# BG1094_Connector.net
KiCad netlist of a schematic drawn in Altium Designer
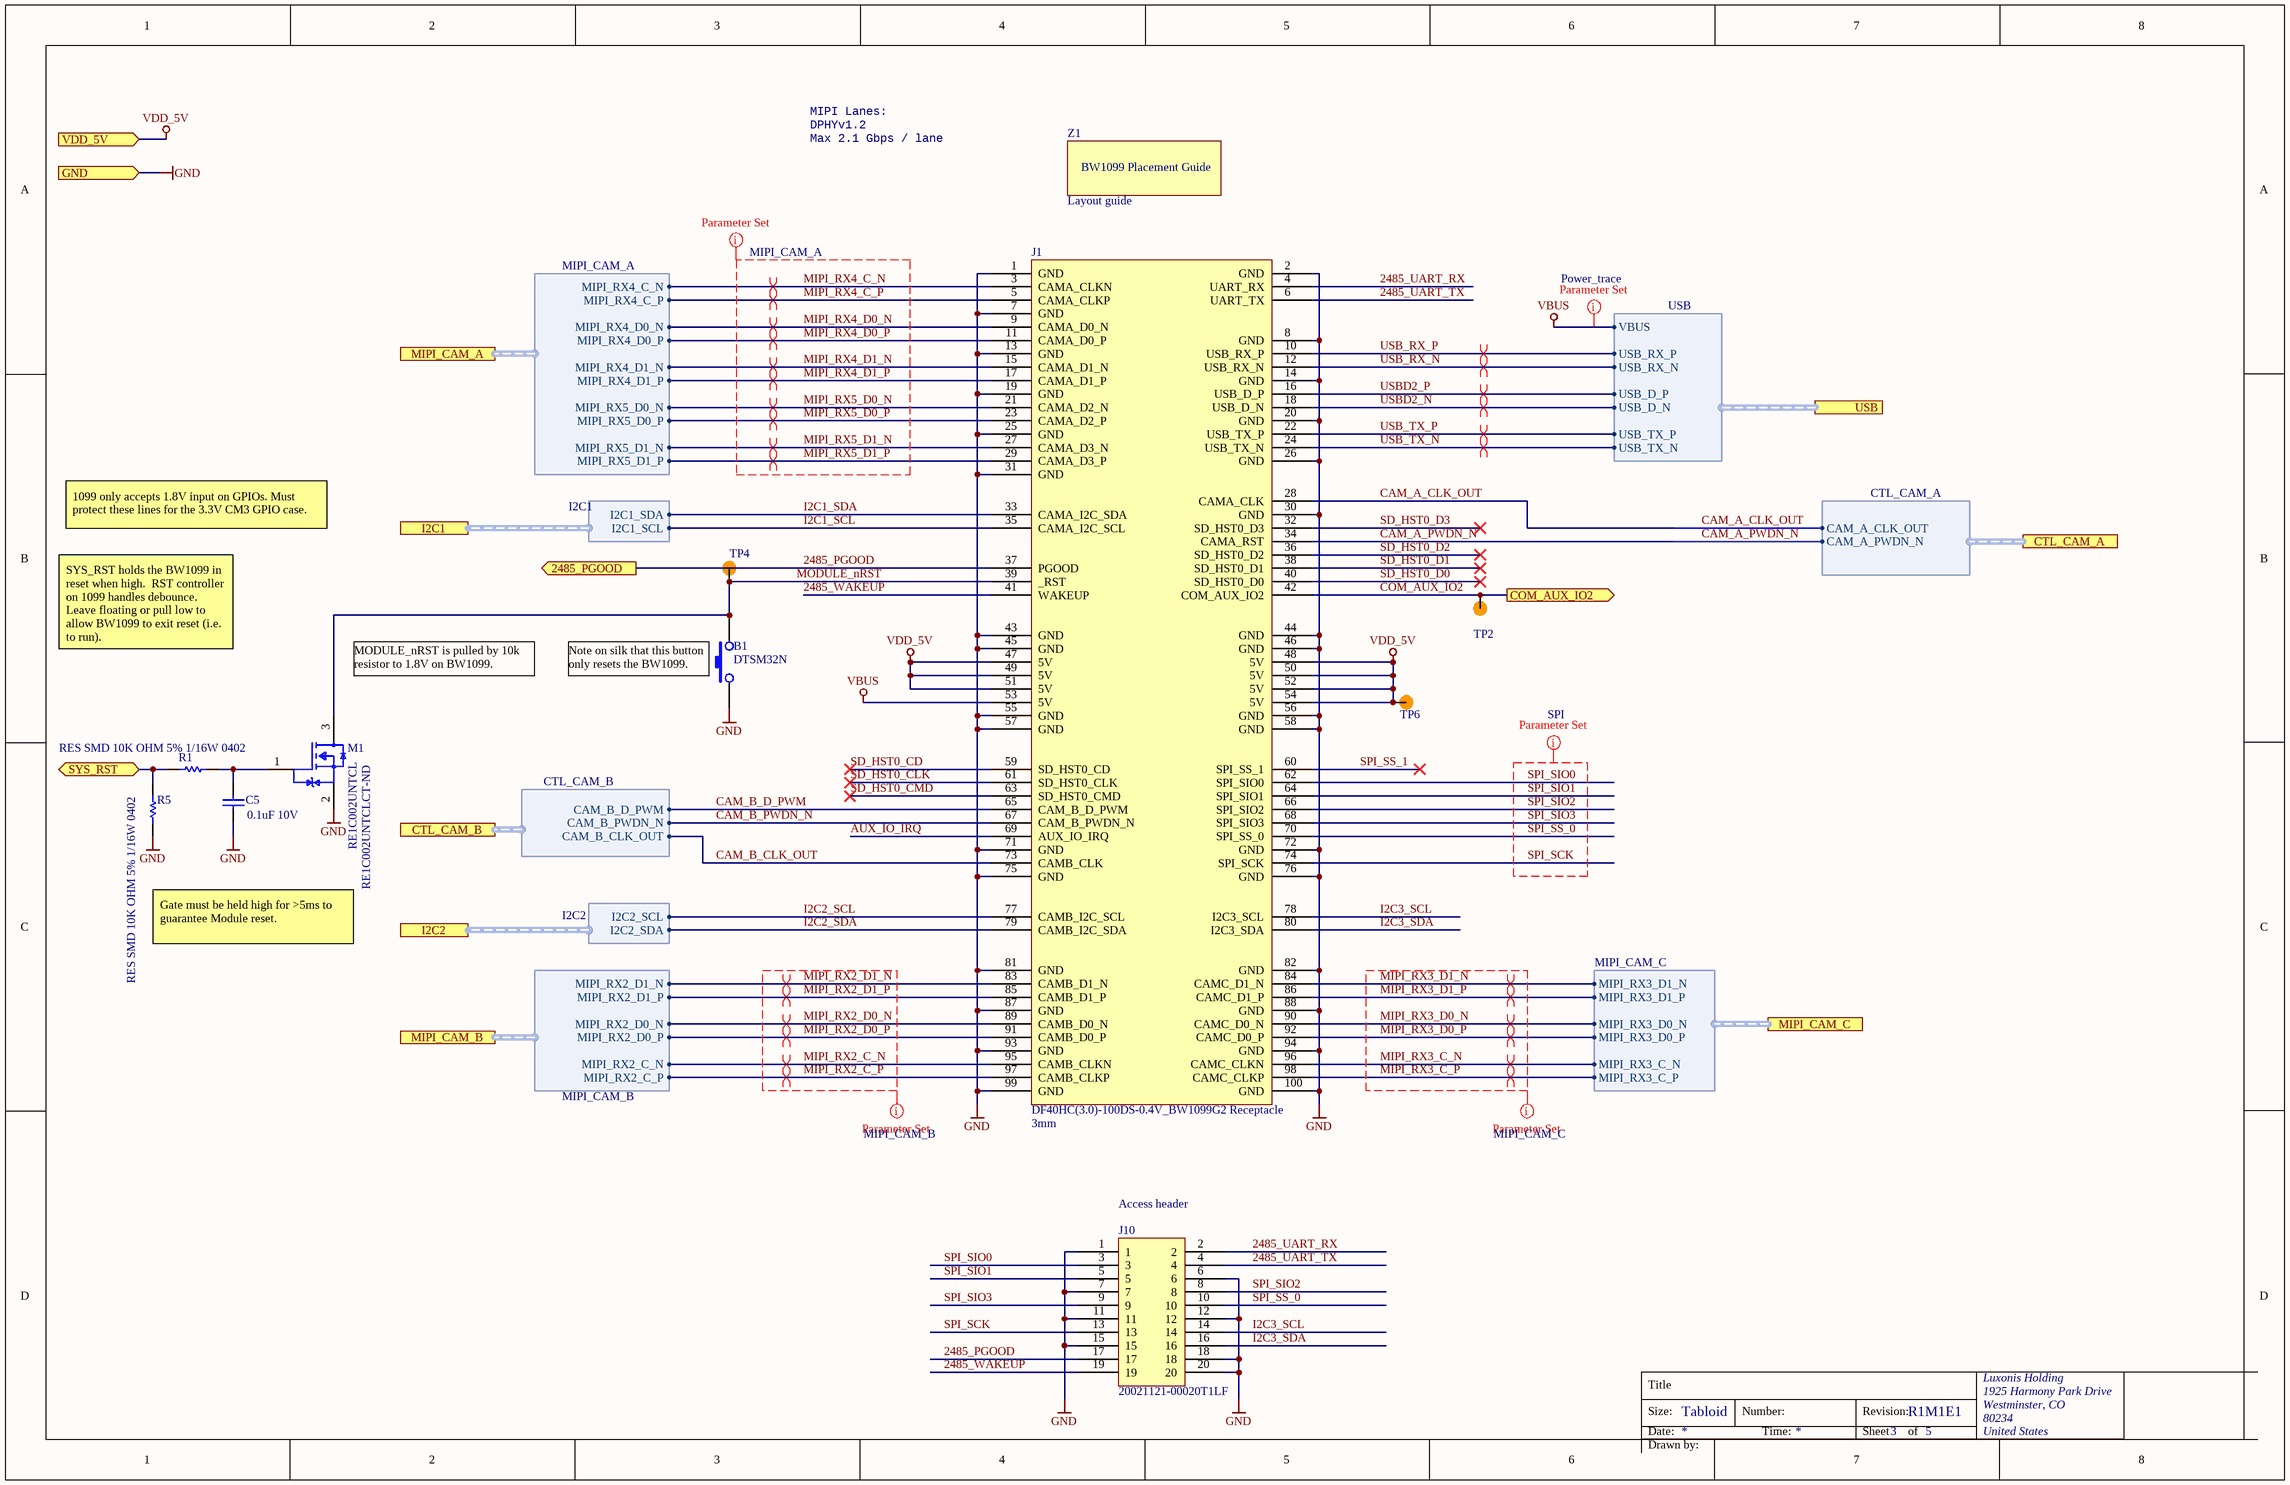
[diagram p0: BG1094_Connector.SchDoc]

(export (version "E")
  (design (tool "Eeschema 10.0.6"))
  (components
    (comp (ref "B1")
      (value "DTSM32N")
      (footprint "DTSM32N")
      (description "Tact Switch")
      (libsource (lib "MV0235_R4M0E0") (part "SW-PB"))
    )
    (comp (ref "C5")
      (value "0.1uF 10V")
      (footprint "IPC_RES_CAP:CAPC0402(1005)70_N")
      (description "0.1uF 10V X7R 10% Pad SMD 0402 125C T/R")
      (fields (field (name "TOLERANCE") "10%") (field (name "VOLTAGE") "10V"))
      (libsource (lib "Luxonis") (part "!CAP"))
    )
    (comp (ref "J1")
      (value "DF40HC(3.0)-100DS-0.4V_BW1099G2 Receptacle")
      (footprint "LuxonisMaster:DF40HC-3.0-100DS-0.4V_minpad")
      (description "CONN RCPT 100POS 0.4MM SMD GOLD")
      (fields (field (name "MATED STACKING HEIGHT") "3mm"))
      (libsource (lib "LuxonisMaster") (part "DF40HC(3.0)-100DS-0.4V_BW1099_G2"))
    )
    (comp (ref "J10")
      (value "20021121-00020T1LF")
      (footprint "BG1094:20021121-00020T1LF")
      (description "Conn Unshrouded Header HDR 20 POS 1.27mm Solder ST SMD Tube")
      (libsource (lib "BG1094") (part "20021121-00020T1LF"))
    )
    (comp (ref "M1")
      (value "RE1C002UNTCL")
      (footprint "Luxonis:SOT-416FL")
      (description "MOSFET N-CH 20V 0.2A EMT3")
      (fields (field (name "SUPPLIER PART NUMBER 1") "RE1C002UNTCLCT-ND"))
      (libsource (lib "Luxonis") (part "RE1C002UNTCL"))
    )
    (comp (ref "R1")
      (value "RES SMD 10K OHM 5% 1/16W 0402")
      (footprint "RESC0402(1005)_N")
      (libsource (lib "Luxonis") (part "!RES"))
    )
    (comp (ref "R5")
      (value "RES SMD 10K OHM 5% 1/16W 0402")
      (footprint "RESC0402(1005)_N")
      (libsource (lib "Luxonis") (part "!RES"))
    )
    (comp (ref "TP2")
      (value "TP100_200_NS")
      (footprint "LuxonisMaster:TP100_200_NS")
      (libsource (lib "LuxonisMaster") (part "TEST_POINT"))
    )
    (comp (ref "TP4")
      (value "TP_SMD")
      (footprint "TP_0.75MM_SMD_NO-SILK")
      (description "circular pad test point, SMD")
      (libsource (lib "Luxonis") (part "TP_SMD"))
    )
    (comp (ref "TP6")
      (value "TP_SMD")
      (footprint "TP_0.75MM_SMD_NO-SILK")
      (description "circular pad test point, SMD")
      (libsource (lib "Luxonis") (part "TP_SMD"))
    )
    (comp (ref "Z1")
      (value "Layout guide")
      (footprint "Luxonis:BW1099_Footprint")
      (description "Use for aligning BW1099 mount")
      (libsource (lib "Luxonis") (part "BW1099_Footprint"))
    )
  )
  (nets
    (net (code "9") (name "/2485_PGOOD") (class "Default")
      (node (ref "J1") (pin "37") (pinfunction "PGOOD_37") (pintype "passive"))
      (node (ref "J10") (pin "17") (pinfunction "17_17") (pintype "passive"))
    )
    (net (code "10") (name "/2485_UART_RX") (class "Default")
      (node (ref "J1") (pin "4") (pinfunction "UART_RX_4") (pintype "passive"))
      (node (ref "J10") (pin "2") (pinfunction "2_2") (pintype "passive"))
    )
    (net (code "11") (name "/2485_UART_TX") (class "Default")
      (node (ref "J1") (pin "6") (pinfunction "UART_TX_6") (pintype "passive"))
      (node (ref "J10") (pin "4") (pinfunction "4_4") (pintype "passive"))
    )
    (net (code "12") (name "/2485_WAKEUP") (class "Default")
      (node (ref "J1") (pin "41") (pinfunction "WAKEUP_41") (pintype "passive"))
      (node (ref "J10") (pin "19") (pinfunction "19_19") (pintype "passive"))
    )
    (net (code "13") (name "/AUX_IO_IRQ") (class "Default")
      (node (ref "J1") (pin "69") (pinfunction "AUX_IO_IRQ_69") (pintype "passive"))
    )
    (net (code "14") (name "/CAM_A_CLK_OUT") (class "Default")
      (node (ref "J1") (pin "28") (pinfunction "CAMA_CLK_28") (pintype "passive"))
    )
    (net (code "15") (name "/CAM_A_PWDN_N") (class "Default")
      (node (ref "J1") (pin "34") (pinfunction "CAMA_RST_34") (pintype "passive"))
    )
    (net (code "16") (name "/CAM_B_CLK_OUT") (class "Default")
      (node (ref "J1") (pin "73") (pinfunction "CAMB_CLK_73") (pintype "passive"))
    )
    (net (code "17") (name "/CAM_B_D_PWM") (class "Default")
      (node (ref "J1") (pin "65") (pinfunction "CAM_B_D_PWM_65") (pintype "passive"))
    )
    (net (code "18") (name "/CAM_B_PWDN_N") (class "Default")
      (node (ref "J1") (pin "67") (pinfunction "CAM_B_PWDN_N_67") (pintype "passive"))
    )
    (net (code "19") (name "/COM_AUX_IO2") (class "Default")
      (node (ref "J1") (pin "42") (pinfunction "COM_AUX_IO2_42") (pintype "passive"))
      (node (ref "TP2") (pin "1") (pintype "passive"))
    )
    (net (code "20") (name "/I2C1_SCL") (class "Default")
      (node (ref "J1") (pin "35") (pinfunction "CAMA_I2C_SCL_35") (pintype "passive"))
    )
    (net (code "21") (name "/I2C1_SDA") (class "Default")
      (node (ref "J1") (pin "33") (pinfunction "CAMA_I2C_SDA_33") (pintype "passive"))
    )
    (net (code "22") (name "/I2C2_SCL") (class "Default")
      (node (ref "J1") (pin "77") (pinfunction "CAMB_I2C_SCL_77") (pintype "passive"))
    )
    (net (code "23") (name "/I2C2_SDA") (class "Default")
      (node (ref "J1") (pin "79") (pinfunction "CAMB_I2C_SDA_79") (pintype "passive"))
    )
    (net (code "24") (name "/I2C3_SCL") (class "Default")
      (node (ref "J1") (pin "78") (pinfunction "I2C3_SCL_78") (pintype "passive"))
      (node (ref "J10") (pin "14") (pinfunction "14_14") (pintype "passive"))
    )
    (net (code "25") (name "/I2C3_SDA") (class "Default")
      (node (ref "J1") (pin "80") (pinfunction "I2C3_SDA_80") (pintype "passive"))
      (node (ref "J10") (pin "16") (pinfunction "16_16") (pintype "passive"))
    )
    (net (code "26") (name "/MIPI_RX2_C_N") (class "Default")
      (node (ref "J1") (pin "95") (pinfunction "CAMB_CLKN_95") (pintype "passive"))
    )
    (net (code "27") (name "/MIPI_RX2_C_P") (class "Default")
      (node (ref "J1") (pin "97") (pinfunction "CAMB_CLKP_97") (pintype "passive"))
    )
    (net (code "28") (name "/MIPI_RX2_D0_N") (class "Default")
      (node (ref "J1") (pin "89") (pinfunction "CAMB_D0_N_89") (pintype "passive"))
    )
    (net (code "29") (name "/MIPI_RX2_D0_P") (class "Default")
      (node (ref "J1") (pin "91") (pinfunction "CAMB_D0_P_91") (pintype "passive"))
    )
    (net (code "30") (name "/MIPI_RX2_D1_N") (class "Default")
      (node (ref "J1") (pin "83") (pinfunction "CAMB_D1_N_83") (pintype "passive"))
    )
    (net (code "31") (name "/MIPI_RX2_D1_P") (class "Default")
      (node (ref "J1") (pin "85") (pinfunction "CAMB_D1_P_85") (pintype "passive"))
    )
    (net (code "32") (name "/MIPI_RX3_C_N") (class "Default")
      (node (ref "J1") (pin "96") (pinfunction "CAMC_CLKN_96") (pintype "passive"))
    )
    (net (code "33") (name "/MIPI_RX3_C_P") (class "Default")
      (node (ref "J1") (pin "98") (pinfunction "CAMC_CLKP_98") (pintype "passive"))
    )
    (net (code "34") (name "/MIPI_RX3_D0_N") (class "Default")
      (node (ref "J1") (pin "90") (pinfunction "CAMC_D0_N_90") (pintype "passive"))
    )
    (net (code "35") (name "/MIPI_RX3_D0_P") (class "Default")
      (node (ref "J1") (pin "92") (pinfunction "CAMC_D0_P_92") (pintype "passive"))
    )
    (net (code "36") (name "/MIPI_RX3_D1_N") (class "Default")
      (node (ref "J1") (pin "84") (pinfunction "CAMC_D1_N_84") (pintype "passive"))
    )
    (net (code "37") (name "/MIPI_RX3_D1_P") (class "Default")
      (node (ref "J1") (pin "86") (pinfunction "CAMC_D1_P_86") (pintype "passive"))
    )
    (net (code "38") (name "/MIPI_RX4_C_N") (class "Default")
      (node (ref "J1") (pin "3") (pinfunction "CAMA_CLKN_3") (pintype "passive"))
    )
    (net (code "39") (name "/MIPI_RX4_C_P") (class "Default")
      (node (ref "J1") (pin "5") (pinfunction "CAMA_CLKP_5") (pintype "passive"))
    )
    (net (code "40") (name "/MIPI_RX4_D0_N") (class "Default")
      (node (ref "J1") (pin "9") (pinfunction "CAMA_D0_N_9") (pintype "passive"))
    )
    (net (code "41") (name "/MIPI_RX4_D0_P") (class "Default")
      (node (ref "J1") (pin "11") (pinfunction "CAMA_D0_P_11") (pintype "passive"))
    )
    (net (code "42") (name "/MIPI_RX4_D1_N") (class "Default")
      (node (ref "J1") (pin "15") (pinfunction "CAMA_D1_N_15") (pintype "passive"))
    )
    (net (code "43") (name "/MIPI_RX4_D1_P") (class "Default")
      (node (ref "J1") (pin "17") (pinfunction "CAMA_D1_P_17") (pintype "passive"))
    )
    (net (code "44") (name "/MIPI_RX5_D0_N") (class "Default")
      (node (ref "J1") (pin "21") (pinfunction "CAMA_D2_N_21") (pintype "passive"))
    )
    (net (code "45") (name "/MIPI_RX5_D0_P") (class "Default")
      (node (ref "J1") (pin "23") (pinfunction "CAMA_D2_P_23") (pintype "passive"))
    )
    (net (code "46") (name "/MIPI_RX5_D1_N") (class "Default")
      (node (ref "J1") (pin "27") (pinfunction "CAMA_D3_N_27") (pintype "passive"))
    )
    (net (code "47") (name "/MIPI_RX5_D1_P") (class "Default")
      (node (ref "J1") (pin "29") (pinfunction "CAMA_D3_P_29") (pintype "passive"))
    )
    (net (code "48") (name "/MODULE_nRST") (class "Default")
      (node (ref "B1") (pin "2") (pinfunction "2_2") (pintype "passive"))
      (node (ref "J1") (pin "39") (pinfunction "_RST_39") (pintype "passive"))
      (node (ref "M1") (pin "3") (pinfunction "Drain_3") (pintype "passive"))
      (node (ref "TP4") (pin "1") (pintype "passive"))
    )
    (net (code "49") (name "/SD_HST0_CD") (class "Default")
      (node (ref "J1") (pin "59") (pinfunction "SD_HST0_CD_59") (pintype "passive+no_connect"))
    )
    (net (code "50") (name "/SD_HST0_CLK") (class "Default")
      (node (ref "J1") (pin "61") (pinfunction "SD_HST0_CLK_61") (pintype "passive+no_connect"))
    )
    (net (code "51") (name "/SD_HST0_CMD") (class "Default")
      (node (ref "J1") (pin "63") (pinfunction "SD_HST0_CMD_63") (pintype "passive+no_connect"))
    )
    (net (code "52") (name "/SD_HST0_D0") (class "Default")
      (node (ref "J1") (pin "40") (pinfunction "SD_HST0_D0_40") (pintype "passive+no_connect"))
    )
    (net (code "53") (name "/SD_HST0_D1") (class "Default")
      (node (ref "J1") (pin "38") (pinfunction "SD_HST0_D1_38") (pintype "passive+no_connect"))
    )
    (net (code "54") (name "/SD_HST0_D2") (class "Default")
      (node (ref "J1") (pin "36") (pinfunction "SD_HST0_D2_36") (pintype "passive+no_connect"))
    )
    (net (code "55") (name "/SD_HST0_D3") (class "Default")
      (node (ref "J1") (pin "32") (pinfunction "SD_HST0_D3_32") (pintype "passive+no_connect"))
    )
    (net (code "56") (name "/SPI_SCK") (class "Default")
      (node (ref "J1") (pin "74") (pinfunction "SPI_SCK_74") (pintype "passive"))
      (node (ref "J10") (pin "13") (pinfunction "13_13") (pintype "passive"))
    )
    (net (code "57") (name "/SPI_SIO0") (class "Default")
      (node (ref "J1") (pin "62") (pinfunction "SPI_SIO0_62") (pintype "passive"))
      (node (ref "J10") (pin "3") (pinfunction "3_3") (pintype "passive"))
    )
    (net (code "58") (name "/SPI_SIO1") (class "Default")
      (node (ref "J1") (pin "64") (pinfunction "SPI_SIO1_64") (pintype "passive"))
      (node (ref "J10") (pin "5") (pinfunction "5_5") (pintype "passive"))
    )
    (net (code "59") (name "/SPI_SIO2") (class "Default")
      (node (ref "J1") (pin "66") (pinfunction "SPI_SIO2_66") (pintype "passive"))
      (node (ref "J10") (pin "8") (pinfunction "8_8") (pintype "passive"))
    )
    (net (code "60") (name "/SPI_SIO3") (class "Default")
      (node (ref "J1") (pin "68") (pinfunction "SPI_SIO3_68") (pintype "passive"))
      (node (ref "J10") (pin "9") (pinfunction "9_9") (pintype "passive"))
    )
    (net (code "61") (name "/SPI_SS_0") (class "Default")
      (node (ref "J1") (pin "70") (pinfunction "SPI_SS_0_70") (pintype "passive"))
      (node (ref "J10") (pin "10") (pinfunction "10_10") (pintype "passive"))
    )
    (net (code "62") (name "/SPI_SS_1") (class "Default")
      (node (ref "J1") (pin "60") (pinfunction "SPI_SS_1_60") (pintype "passive+no_connect"))
    )
    (net (code "63") (name "/SYS_RST") (class "Default")
      (node (ref "R1") (pin "2") (pinfunction "2_2") (pintype "passive"))
      (node (ref "R5") (pin "2") (pinfunction "2_2") (pintype "passive"))
    )
    (net (code "64") (name "/USBD2_N") (class "Default")
      (node (ref "J1") (pin "18") (pinfunction "USB_D_N_18") (pintype "passive"))
    )
    (net (code "65") (name "/USBD2_P") (class "Default")
      (node (ref "J1") (pin "16") (pinfunction "USB_D_P_16") (pintype "passive"))
    )
    (net (code "66") (name "/USB_RX_N") (class "Default")
      (node (ref "J1") (pin "12") (pinfunction "USB_RX_N_12") (pintype "passive"))
    )
    (net (code "67") (name "/USB_RX_P") (class "Default")
      (node (ref "J1") (pin "10") (pinfunction "USB_RX_P_10") (pintype "passive"))
    )
    (net (code "68") (name "/USB_TX_N") (class "Default")
      (node (ref "J1") (pin "24") (pinfunction "USB_TX_N_24") (pintype "passive"))
    )
    (net (code "69") (name "/USB_TX_P") (class "Default")
      (node (ref "J1") (pin "22") (pinfunction "USB_TX_P_22") (pintype "passive"))
    )
    (net (code "78") (name "GND") (class "Default")
      (node (ref "B1") (pin "1") (pinfunction "1_1") (pintype "passive"))
      (node (ref "C5") (pin "1") (pinfunction "1_1") (pintype "passive"))
      (node (ref "J1") (pin "1") (pinfunction "GND_1") (pintype "passive"))
      (node (ref "J1") (pin "100") (pinfunction "GND_100") (pintype "passive"))
      (node (ref "J1") (pin "13") (pinfunction "GND_13") (pintype "passive"))
      (node (ref "J1") (pin "14") (pinfunction "GND_14") (pintype "passive"))
      (node (ref "J1") (pin "19") (pinfunction "GND_19") (pintype "passive"))
      (node (ref "J1") (pin "2") (pinfunction "GND_2") (pintype "passive"))
      (node (ref "J1") (pin "20") (pinfunction "GND_20") (pintype "passive"))
      (node (ref "J1") (pin "25") (pinfunction "GND_25") (pintype "passive"))
      (node (ref "J1") (pin "26") (pinfunction "GND_26") (pintype "passive"))
      (node (ref "J1") (pin "30") (pinfunction "GND_30") (pintype "passive"))
      (node (ref "J1") (pin "31") (pinfunction "GND_31") (pintype "passive"))
      (node (ref "J1") (pin "43") (pinfunction "GND_43") (pintype "passive"))
      (node (ref "J1") (pin "44") (pinfunction "GND_44") (pintype "passive"))
      (node (ref "J1") (pin "45") (pinfunction "GND_45") (pintype "passive"))
      (node (ref "J1") (pin "46") (pinfunction "GND_46") (pintype "passive"))
      (node (ref "J1") (pin "55") (pinfunction "GND_55") (pintype "passive"))
      (node (ref "J1") (pin "56") (pinfunction "GND_56") (pintype "passive"))
      (node (ref "J1") (pin "57") (pinfunction "GND_57") (pintype "passive"))
      (node (ref "J1") (pin "58") (pinfunction "GND_58") (pintype "passive"))
      (node (ref "J1") (pin "7") (pinfunction "GND_7") (pintype "passive"))
      (node (ref "J1") (pin "71") (pinfunction "GND_71") (pintype "passive"))
      (node (ref "J1") (pin "72") (pinfunction "GND_72") (pintype "passive"))
      (node (ref "J1") (pin "75") (pinfunction "GND_75") (pintype "passive"))
      (node (ref "J1") (pin "76") (pinfunction "GND_76") (pintype "passive"))
      (node (ref "J1") (pin "8") (pinfunction "GND_8") (pintype "passive"))
      (node (ref "J1") (pin "81") (pinfunction "GND_81") (pintype "passive"))
      (node (ref "J1") (pin "82") (pinfunction "GND_82") (pintype "passive"))
      (node (ref "J1") (pin "87") (pinfunction "GND_87") (pintype "passive"))
      (node (ref "J1") (pin "88") (pinfunction "GND_88") (pintype "passive"))
      (node (ref "J1") (pin "93") (pinfunction "GND_93") (pintype "passive"))
      (node (ref "J1") (pin "94") (pinfunction "GND_94") (pintype "passive"))
      (node (ref "J1") (pin "99") (pinfunction "GND_99") (pintype "passive"))
      (node (ref "J10") (pin "1") (pinfunction "1_1") (pintype "passive"))
      (node (ref "J10") (pin "11") (pinfunction "11_11") (pintype "passive"))
      (node (ref "J10") (pin "12") (pinfunction "12_12") (pintype "passive"))
      (node (ref "J10") (pin "15") (pinfunction "15_15") (pintype "passive"))
      (node (ref "J10") (pin "18") (pinfunction "18_18") (pintype "passive"))
      (node (ref "J10") (pin "20") (pinfunction "20_20") (pintype "passive"))
      (node (ref "J10") (pin "6") (pinfunction "6_6") (pintype "passive"))
      (node (ref "J10") (pin "7") (pinfunction "7_7") (pintype "passive"))
      (node (ref "M1") (pin "2") (pinfunction "Source_2") (pintype "passive"))
      (node (ref "R5") (pin "1") (pinfunction "1_1") (pintype "passive"))
    )
    (net (code "79") (name "Net-(M1-Gate)") (class "Default")
      (node (ref "C5") (pin "2") (pinfunction "2_2") (pintype "passive"))
      (node (ref "M1") (pin "1") (pinfunction "Gate_1") (pintype "passive"))
      (node (ref "R1") (pin "1") (pinfunction "1_1") (pintype "passive"))
    )
    (net (code "80") (name "VBUS") (class "Default")
      (node (ref "J1") (pin "53") (pinfunction "5V_53") (pintype "passive"))
    )
    (net (code "81") (name "VDD_5V") (class "Default")
      (node (ref "J1") (pin "47") (pinfunction "5V_47") (pintype "passive"))
      (node (ref "J1") (pin "48") (pinfunction "5V_48") (pintype "passive"))
      (node (ref "J1") (pin "49") (pinfunction "5V_49") (pintype "passive"))
      (node (ref "J1") (pin "50") (pinfunction "5V_50") (pintype "passive"))
      (node (ref "J1") (pin "51") (pinfunction "5V_51") (pintype "passive"))
      (node (ref "J1") (pin "52") (pinfunction "5V_52") (pintype "passive"))
      (node (ref "J1") (pin "54") (pinfunction "5V_54") (pintype "passive"))
      (node (ref "TP6") (pin "1") (pintype "passive"))
    )
  )
)
